# 24Vto5V.net
KiCad netlist of a schematic drawn in Altium Designer
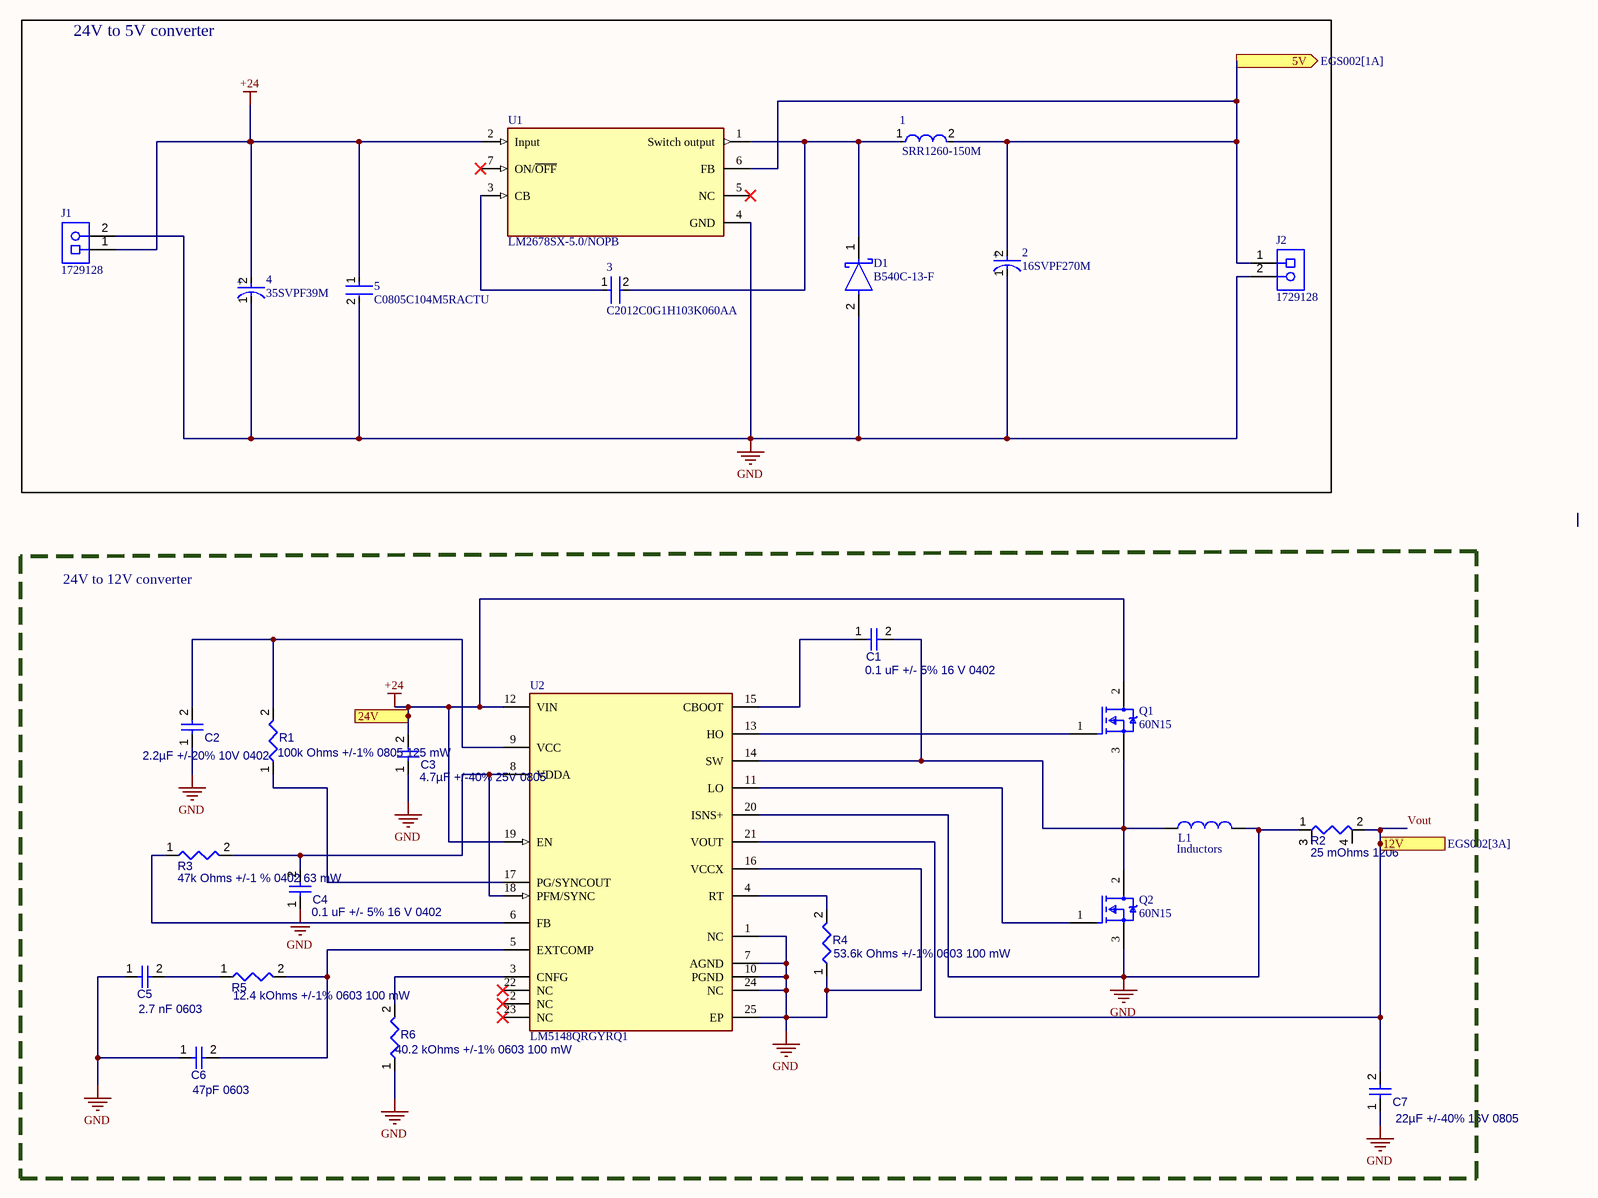
[diagram p0: 24Vto5V.SchDoc]

(export (version "E")
  (design (tool "Eeschema 10.0.6"))
  (components
    (comp (ref "1")
      (value "SRR1260-150M")
      (footprint "FP-SRR1260-MFG")
      (description "FIXED IND 15UH 5A 27 MOHM SMD")
      (fields (field (name "TOLERANCE") "20%"))
      (libsource (lib "Altium Content Vault") (part "725321dda6339637d4d059423bc1c3c"))
    )
    (comp (ref "2")
      (value "16SVPF270M")
      (footprint "FP-OS-CON-SMT-E7-MFG")
      (description "Conductive Polymer Aluminum Solid Capacitors (OS-CON) 270uF ±20% 16V RADIAL SMT 8x6.9mm")
      (fields (field (name "VOLTAGE") "16V") (field (name "TOLERANCE") "20%"))
      (libsource (lib "Altium Content Vault") (part "cf48714ba7e38822c1575c7ec0b6d1f"))
    )
    (comp (ref "3")
      (value "C2012C0G1H103K060AA")
      (footprint "FP-C2012-060-0_2-IPC_A")
      (description "Multilayer Ceramic Capacitors 10nF ±10% 50V C0G SMD 0805")
      (fields (field (name "TOLERANCE") "10%"))
      (libsource (lib "Altium Content Vault") (part "b4654b650e69147ec39a6b967a45e02"))
    )
    (comp (ref "4")
      (value "35SVPF39M")
      (footprint "FP-OS-CON-SMT-E7-MFG")
      (description "Conductive Polymer Aluminum Solid Capacitors (OS-CON) 39uF ±20% 35V RADIAL SMT 8x6.9mm")
      (fields (field (name "TOLERANCE") "20%") (field (name "VOLTAGE") "35V"))
      (libsource (lib "Altium Content Vault") (part "cf48714ba7e38822c1575c7ec0b6d1f"))
    )
    (comp (ref "5")
      (value "C0805C104M5RACTU")
      (footprint "FP-C0805C-DN-MFG")
      (description "CAP CER 0.1UF 50V X7R 0805")
      (fields
        (field (name "TOLERANCE") "0.2")
        (field (name "OCTOPART") "https://octopart.com/c0805c104m5ractu-kemet-129379")
      )
      (libsource (lib "Altium Content Vault") (part "b4654b650e69147ec39a6b967a45e02"))
    )
    (comp (ref "C1")
      (value "0.1 uF +/- 5% 16 V 0402")
      (footprint "CAPC1005X56X25LL10T15")
      (description "Chip Capacitor, 0.1 uF, +/- 5%, 16 V, 0402 (1005 Metric)")
      (fields (field (name "TOLERANCE") "5%"))
      (libsource (lib "Rahulb 23") (part "CAP-NP-2"))
    )
    (comp (ref "C2")
      (value "2.2µF +/-20% 10V 0402")
      (footprint "CAPC0402(1005)60_L")
      (description "Chip Capacitor, 2,2µF +/-20%, 10V, 0402, Thickness 0.6 mm")
      (fields (field (name "TOLERANCE") "10%"))
      (libsource (lib "Rahulb 23") (part "CAP-NP-2"))
    )
    (comp (ref "C3")
      (value "4.7µF +/-40% 25V 0805")
      (footprint "CAPC0805(2012)145_L")
      (description "Chip Capacitor, 4.7µF +/-40%, 25V, 0805, Thickness 1.45 mm")
      (fields (field (name "TOLERANCE") "20%"))
      (libsource (lib "Rahulb 23") (part "CAP-NP-2"))
    )
    (comp (ref "C4")
      (value "0.1 uF +/- 5% 16 V 0402")
      (footprint "CAPC1005X56X25LL10T15")
      (description "Chip Capacitor, 0.1 uF, +/- 5%, 16 V, 0402 (1005 Metric)")
      (fields (field (name "TOLERANCE") "5%"))
      (libsource (lib "Rahulb 23") (part "CAP-NP-2"))
    )
    (comp (ref "C5")
      (value "2.7 nF 0603")
      (footprint "CAPC1608X87X35NL15T15")
      (description "Chip Capacitor, 10 pF, +/- 0.25 pF, 50 V, 0603 (1608 Metric)")
      (fields (field (name "TOLERANCE") "0.25%"))
      (libsource (lib "Rahulb 23") (part "CAP-NP-2"))
    )
    (comp (ref "C6")
      (value "47pF 0603")
      (footprint "CAPC0603(1608)100_L")
      (description "Chip Capacitor, 470nF +/-20%, 25V, 0603, Thickness 1 mm")
      (fields (field (name "TOLERANCE") "10%"))
      (libsource (lib "Rahulb 23") (part "CAP-NP-2"))
    )
    (comp (ref "C7")
      (value "22µF +/-40% 16V 0805")
      (footprint "CAPC0805(2012)145_L")
      (description "Chip Capacitor, 22µF +/-40%, 16V, 0805, Thickness 1.45 mm")
      (fields (field (name "TOLERANCE") "5%"))
      (libsource (lib "Rahulb 23") (part "CAP-NP-2"))
    )
    (comp (ref "D1")
      (value "B540C-13-F")
      (footprint "FP-SMC-MFG")
      (description "DIODE SCHOTTKY 40V 5A SMC")
      (fields
        (field (name "OCTOPART") "https://octopart.com/b540c-13-f-diodes+inc.-325873")
        (field (name "MANUFACTURER") "Diodes Inc.")
      )
      (libsource (lib "Altium Content Vault") (part "1d6ec82d83fb6aee721767c19dac4b9"))
    )
    (comp (ref "J1")
      (value "1729128")
      (footprint "PHOE-1729128-2_V")
      (description "PCB Terminal Block, 13.5 A, 400 V, 2-Pin THD, RoHS, Bulk")
      (fields (field (name "MANUFACTURER") "Phoenix Contact"))
      (libsource (lib "") (part "CN-2P-F-R2_1"))
    )
    (comp (ref "J2")
      (value "1729128")
      (footprint "PHOE-1729128-2_V")
      (description "PCB Terminal Block, 13.5 A, 400 V, 2-Pin THD, RoHS, Bulk")
      (fields (field (name "MANUFACTURER") "Phoenix Contact"))
      (libsource (lib "Altium Content Vault") (part "CN-2P-F-R2"))
    )
    (comp (ref "L1") (value "Inductors") (description "24.65uH") (libsource (lib "Rahulb 23") (part "IND-2")))
    (comp (ref "Q1")
      (value "60N15")
      (footprint "FP-TO-220AB-MFG")
      (description "60N15 150V 60A N-Channel MOSFET TO-220")
      (libsource (lib "Altium Content Vault") (part "8b62d417cbef8344eebe0bde0c45977"))
    )
    (comp (ref "Q2")
      (value "60N15")
      (footprint "FP-TO-220AB-MFG")
      (description "60N15 150V 60A N-Channel MOSFET TO-220")
      (libsource (lib "Altium Content Vault") (part "8b62d417cbef8344eebe0bde0c45977"))
    )
    (comp (ref "R1")
      (value "100k Ohms +/-1% 0805 125 mW")
      (footprint "RESC2013X70X40ML20T20")
      (description "Chip Resistor, 100 KOhm, +/- 1%, 0.125 W, -55 to 155 degC, 0805 (2012 Metric)")
      (fields (field (name "TOLERANCE") "1%") (field (name "POWER") "125mW"))
      (libsource (lib "Rahulb 23") (part "RES-2"))
    )
    (comp (ref "R2")
      (value "25 mOhms 1206")
      (footprint "SUSUMU-3216T4A")
      (description "Chip Resistor, 0,007 Ohms, +/-1%, 63 mW, -55 to 155 degC, 1206")
      (fields (field (name "TOLERANCE") "1%"))
      (libsource (lib "Rahulb 23") (part "RES-4"))
    )
    (comp (ref "R3")
      (value "47k Ohms +/-1 % 0402 63 mW")
      (footprint "RESC0402(1005)_L")
      (description "Chip Resistor, 47,5 kOhms, +/-1 %, 63 mW, -55 to 155 degC, 0402")
      (fields (field (name "TOLERANCE") "1%") (field (name "POWER") "63mW"))
      (libsource (lib "Rahulb 23") (part "RES-2"))
    )
    (comp (ref "R4")
      (value "53.6k Ohms +/-1% 0603 100 mW")
      (footprint "RESC1608X55X25ML10T15")
      (description "Chip Resistor, 10 KOhm, +/- 1%, 01 W, -55 to 155 degC, 0603 (1608 Metric)")
      (fields (field (name "TOLERANCE") "1%") (field (name "POWER") "100mW"))
      (libsource (lib "Rahulb 23") (part "RES-2"))
    )
    (comp (ref "R5")
      (value "12.4 kOhms +/-1% 0603 100 mW")
      (footprint "RESC1608X55X25ML10T15")
      (description "Chip Resistor, 10 KOhm, +/- 1%, 01 W, -55 to 155 degC, 0603 (1608 Metric)")
      (fields (field (name "TOLERANCE") "1%") (field (name "POWER") "100mW"))
      (libsource (lib "Rahulb 23") (part "RES-2"))
    )
    (comp (ref "R6")
      (value "40.2 kOhms +/-1% 0603 100 mW")
      (footprint "RESC1608X55X25ML10T15")
      (description "Chip Resistor, 10 KOhm, +/- 1%, 01 W, -55 to 155 degC, 0603 (1608 Metric)")
      (fields (field (name "TOLERANCE") "1%") (field (name "POWER") "100mW"))
      (libsource (lib "Rahulb 23") (part "RES-2"))
    )
    (comp (ref "U1")
      (value "LM2678SX-5.0/NOPB")
      (footprint "FP-KTW0007B-MFG")
      (description "IC REG BUCK 5V 5A TO263-7")
      (libsource (lib "Altium Content Vault") (part "7e88065a8287dcd79b9e61a875172dc"))
    )
    (comp (ref "U2")
      (value "LM5148QRGYRQ1")
      (footprint "FP-RGY0024E-MFG")
      (libsource (lib "Altium Content Vault") (part "ab60acdb83b3e8c6cb53feaa4ccc0a4"))
    )
  )
  (nets
    (net (code "1") (name "+24") (class "Default")
      (node (ref "4") (pin "2") (pinfunction "A_2") (pintype "passive"))
      (node (ref "5") (pin "1") (pinfunction "1_1") (pintype "passive"))
      (node (ref "C3") (pin "2") (pinfunction "2_2") (pintype "passive"))
      (node (ref "J1") (pin "1") (pinfunction "1_1") (pintype "passive"))
      (node (ref "Q1") (pin "2") (pinfunction "DRAIN_2") (pintype "passive"))
      (node (ref "U1") (pin "2") (pinfunction "Input_2") (pintype "input"))
      (node (ref "U2") (pin "12") (pinfunction "VIN_12") (pintype "power_in"))
      (node (ref "U2") (pin "19") (pinfunction "EN_19") (pintype "input"))
    )
    (net (code "2") (name "/5V") (class "Default")
      (node (ref "1") (pin "2") (pinfunction "2_2") (pintype "passive"))
      (node (ref "2") (pin "2") (pinfunction "A_2") (pintype "passive"))
      (node (ref "J2") (pin "1") (pinfunction "1_1") (pintype "passive"))
      (node (ref "U1") (pin "6") (pinfunction "FB_6") (pintype "passive"))
    )
    (net (code "3") (name "/Vout") (class "Default")
      (node (ref "C7") (pin "2") (pinfunction "2_2") (pintype "passive"))
      (node (ref "R2") (pin "2") (pinfunction "I2_2") (pintype "passive"))
      (node (ref "U2") (pin "21") (pinfunction "VOUT_21") (pintype "passive"))
    )
    (net (code "4") (name "GND") (class "Default")
      (node (ref "2") (pin "1") (pinfunction "C_1") (pintype "passive"))
      (node (ref "4") (pin "1") (pinfunction "C_1") (pintype "passive"))
      (node (ref "5") (pin "2") (pinfunction "2_2") (pintype "passive"))
      (node (ref "C2") (pin "1") (pinfunction "1_1") (pintype "passive"))
      (node (ref "C3") (pin "1") (pinfunction "1_1") (pintype "passive"))
      (node (ref "C4") (pin "1") (pinfunction "1_1") (pintype "passive"))
      (node (ref "C5") (pin "1") (pinfunction "1_1") (pintype "passive"))
      (node (ref "C6") (pin "1") (pinfunction "1_1") (pintype "passive"))
      (node (ref "C7") (pin "1") (pinfunction "1_1") (pintype "passive"))
      (node (ref "D1") (pin "2") (pinfunction "A_2") (pintype "passive"))
      (node (ref "J1") (pin "2") (pinfunction "2_2") (pintype "passive"))
      (node (ref "J2") (pin "2") (pinfunction "2_2") (pintype "passive"))
      (node (ref "L1") (pin "2") (pinfunction "2_2") (pintype "passive"))
      (node (ref "Q2") (pin "3") (pinfunction "SOURCE_3") (pintype "passive"))
      (node (ref "R2") (pin "1") (pinfunction "I1_1") (pintype "passive"))
      (node (ref "R4") (pin "1") (pinfunction "1_1") (pintype "passive"))
      (node (ref "R6") (pin "1") (pinfunction "1_1") (pintype "passive"))
      (node (ref "U1") (pin "4") (pinfunction "GND_4") (pintype "power_in"))
      (node (ref "U2") (pin "1") (pinfunction "NC_1") (pintype "passive"))
      (node (ref "U2") (pin "10") (pinfunction "PGND_10") (pintype "power_in"))
      (node (ref "U2") (pin "16") (pinfunction "VCCX_16") (pintype "power_in"))
      (node (ref "U2") (pin "20") (pinfunction "ISNS+_20") (pintype "passive"))
      (node (ref "U2") (pin "24") (pinfunction "NC_24") (pintype "passive"))
      (node (ref "U2") (pin "25") (pinfunction "EP_25") (pintype "passive"))
      (node (ref "U2") (pin "7") (pinfunction "AGND_7") (pintype "power_in"))
    )
    (net (code "5") (name "Net-(C5-Pad2)") (class "Default")
      (node (ref "C5") (pin "2") (pinfunction "2_2") (pintype "passive"))
      (node (ref "R5") (pin "1") (pinfunction "1_1") (pintype "passive"))
    )
    (net (code "6") (name "Net-(D1-C)") (class "Default")
      (node (ref "1") (pin "1") (pinfunction "1_1") (pintype "passive"))
      (node (ref "3") (pin "2") (pinfunction "2_2") (pintype "passive"))
      (node (ref "D1") (pin "1") (pinfunction "C_1") (pintype "passive"))
      (node (ref "U1") (pin "1") (pinfunction "Switch_output_1") (pintype "output"))
    )
    (net (code "7") (name "Net-(Q1-GATE)") (class "Default")
      (node (ref "Q1") (pin "1") (pinfunction "GATE_1") (pintype "passive"))
      (node (ref "U2") (pin "13") (pinfunction "HO_13") (pintype "passive"))
    )
    (net (code "8") (name "Net-(Q1-SOURCE)") (class "Default")
      (node (ref "C1") (pin "2") (pinfunction "2_2") (pintype "passive"))
      (node (ref "L1") (pin "1") (pinfunction "1_1") (pintype "passive"))
      (node (ref "Q1") (pin "3") (pinfunction "SOURCE_3") (pintype "passive"))
      (node (ref "Q2") (pin "2") (pinfunction "DRAIN_2") (pintype "passive"))
      (node (ref "U2") (pin "14") (pinfunction "SW_14") (pintype "power_in"))
    )
    (net (code "9") (name "Net-(Q2-GATE)") (class "Default")
      (node (ref "Q2") (pin "1") (pinfunction "GATE_1") (pintype "passive"))
      (node (ref "U2") (pin "11") (pinfunction "LO_11") (pintype "passive"))
    )
    (net (code "10") (name "Net-(U1-CB)") (class "Default")
      (node (ref "3") (pin "1") (pinfunction "1_1") (pintype "passive"))
      (node (ref "U1") (pin "3") (pinfunction "CB_3") (pintype "input"))
    )
    (net (code "11") (name "Net-(U2-CBOOT)") (class "Default")
      (node (ref "C1") (pin "1") (pinfunction "1_1") (pintype "passive"))
      (node (ref "U2") (pin "15") (pinfunction "CBOOT_15") (pintype "power_in"))
    )
    (net (code "12") (name "Net-(U2-CNFG)") (class "Default")
      (node (ref "R6") (pin "2") (pinfunction "2_2") (pintype "passive"))
      (node (ref "U2") (pin "3") (pinfunction "CNFG_3") (pintype "passive"))
    )
    (net (code "13") (name "Net-(U2-EXTCOMP)") (class "Default")
      (node (ref "C6") (pin "2") (pinfunction "2_2") (pintype "passive"))
      (node (ref "R5") (pin "2") (pinfunction "2_2") (pintype "passive"))
      (node (ref "U2") (pin "5") (pinfunction "EXTCOMP_5") (pintype "passive"))
    )
    (net (code "14") (name "Net-(U2-FB)") (class "Default")
      (node (ref "R3") (pin "1") (pinfunction "1_1") (pintype "passive"))
      (node (ref "U2") (pin "6") (pinfunction "FB_6") (pintype "passive"))
    )
    (net (code "15") (name "Net-(U2-PFM{slash}SYNC)") (class "Default")
      (node (ref "C4") (pin "2") (pinfunction "2_2") (pintype "passive"))
      (node (ref "R3") (pin "2") (pinfunction "2_2") (pintype "passive"))
      (node (ref "U2") (pin "18") (pinfunction "PFM/SYNC_18") (pintype "input"))
      (node (ref "U2") (pin "8") (pinfunction "VDDA_8") (pintype "passive"))
    )
    (net (code "16") (name "Net-(U2-PG{slash}SYNCOUT)") (class "Default")
      (node (ref "R1") (pin "1") (pinfunction "1_1") (pintype "passive"))
      (node (ref "U2") (pin "17") (pinfunction "PG/SYNCOUT_17") (pintype "open_collector"))
    )
    (net (code "17") (name "Net-(U2-RT)") (class "Default")
      (node (ref "R4") (pin "2") (pinfunction "2_2") (pintype "passive"))
      (node (ref "U2") (pin "4") (pinfunction "RT_4") (pintype "passive"))
    )
    (net (code "18") (name "Net-(U2-VCC)") (class "Default")
      (node (ref "C2") (pin "2") (pinfunction "2_2") (pintype "passive"))
      (node (ref "R1") (pin "2") (pinfunction "2_2") (pintype "passive"))
      (node (ref "U2") (pin "9") (pinfunction "VCC_9") (pintype "power_in"))
    )
    (net (code "19") (name "unconnected-(R2-E1-Pad3)") (class "Default")
      (node (ref "R2") (pin "3") (pinfunction "E1_3") (pintype "passive"))
    )
    (net (code "20") (name "unconnected-(R2-E2-Pad4)") (class "Default")
      (node (ref "R2") (pin "4") (pinfunction "E2_4") (pintype "passive"))
    )
    (net (code "21") (name "unconnected-(U1-NC-Pad5)") (class "Default")
      (node (ref "U1") (pin "5") (pinfunction "NC_5") (pintype "passive+no_connect"))
    )
    (net (code "22") (name "unconnected-(U1-ON{slash}~{OFF}-Pad7)") (class "Default")
      (node (ref "U1") (pin "7") (pinfunction "ON/~{OFF}_7") (pintype "input+no_connect"))
    )
    (net (code "23") (name "unconnected-(U2-NC-Pad2)") (class "Default")
      (node (ref "U2") (pin "2") (pinfunction "NC_2") (pintype "passive+no_connect"))
    )
    (net (code "24") (name "unconnected-(U2-NC-Pad22)") (class "Default")
      (node (ref "U2") (pin "22") (pinfunction "NC_22") (pintype "passive+no_connect"))
    )
    (net (code "25") (name "unconnected-(U2-NC-Pad23)") (class "Default")
      (node (ref "U2") (pin "23") (pinfunction "NC_23") (pintype "passive+no_connect"))
    )
  )
)
